# Regulator_Mechanical.net
KiCad netlist of a schematic drawn in Altium Designer
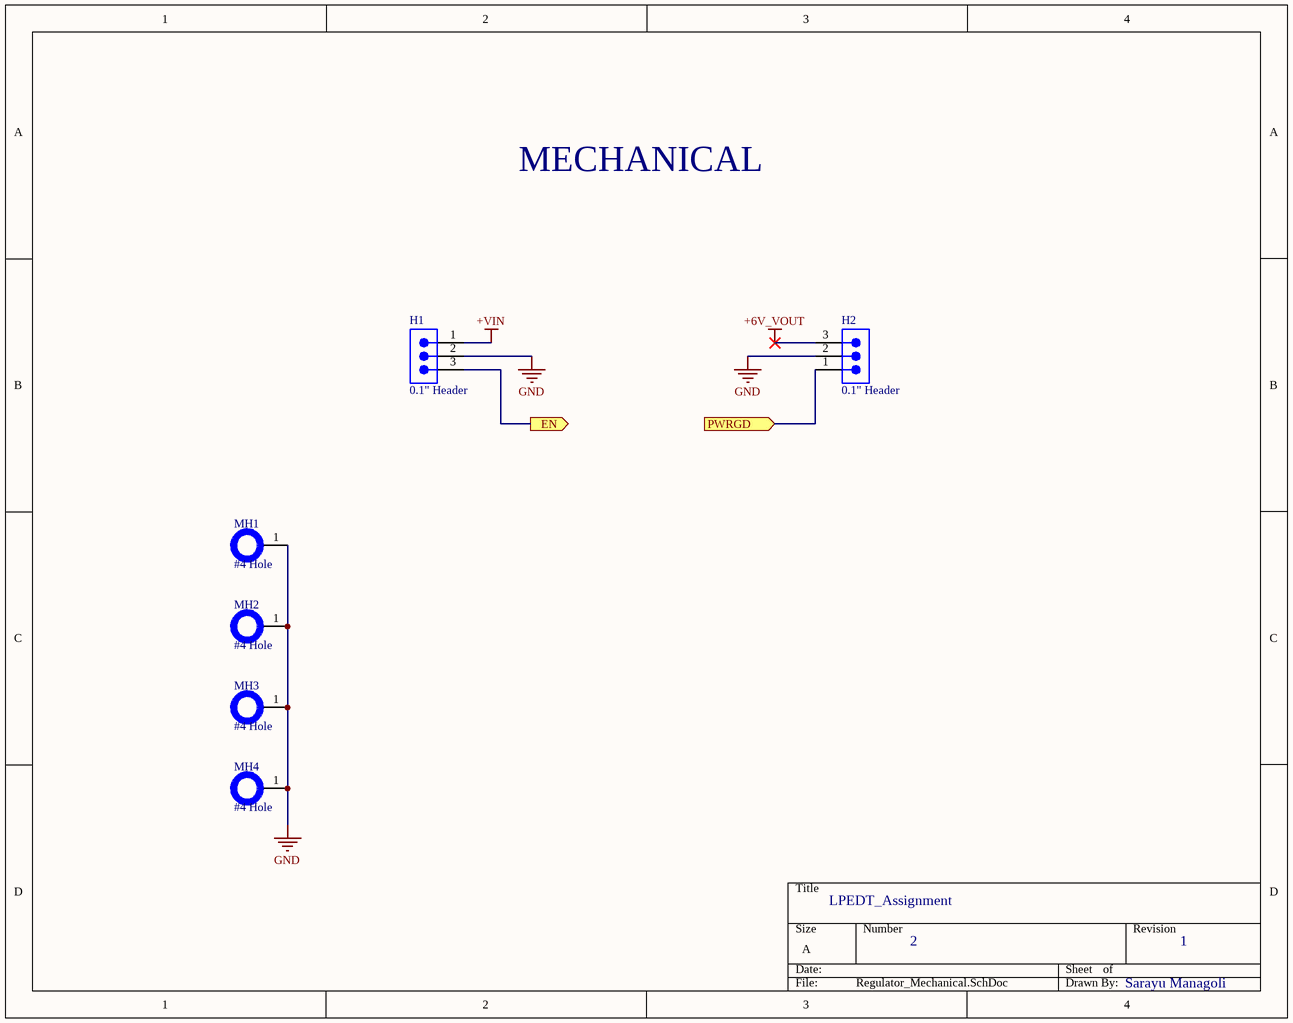
[diagram p0: Regulator_Mechanical.SchDoc]

(export (version "E")
  (design (tool "Eeschema 10.0.6"))
  (components
    (comp (ref "H1")
      (value "0.1\" Header")
      (footprint "3-PIN_MALE_HEADER_01-IN")
      (description "CONN HEADER VERT 3POS 2.54MM")
      (fields
        (field (name "MANUFACTURER") "Sullins")
        (field (name "MANUFACTURER PART NUMBER") "PRPC003SAAN-RC")
      )
      (libsource (lib "LPEDT_Parts") (part "PRPC003SAAN-RC"))
    )
    (comp (ref "H2")
      (value "0.1\" Header")
      (footprint "3-PIN_MALE_HEADER_01-IN")
      (description "CONN HEADER VERT 3POS 2.54MM")
      (fields
        (field (name "MANUFACTURER") "Sullins")
        (field (name "MANUFACTURER PART NUMBER") "PRPC003SAAN-RC")
      )
      (libsource (lib "LPEDT_Parts") (part "PRPC003SAAN-RC"))
    )
    (comp (ref "MH1")
      (value "#4 Hole")
      (footprint "HOLE_#4")
      (libsource (lib "LPEDT_Parts") (part "HOLE_#4"))
    )
    (comp (ref "MH2")
      (value "#4 Hole")
      (footprint "HOLE_#4")
      (libsource (lib "LPEDT_Parts") (part "HOLE_#4"))
    )
    (comp (ref "MH3")
      (value "#4 Hole")
      (footprint "HOLE_#4")
      (libsource (lib "LPEDT_Parts") (part "HOLE_#4"))
    )
    (comp (ref "MH4")
      (value "#4 Hole")
      (footprint "HOLE_#4")
      (libsource (lib "LPEDT_Parts") (part "HOLE_#4"))
    )
  )
  (nets
    (net (code "1") (name "+6V_VOUT") (class "Default")
      (node (ref "H2") (pin "3") (pinfunction "3_3") (pintype "passive"))
    )
    (net (code "2") (name "+VIN") (class "Default")
      (node (ref "H1") (pin "1") (pinfunction "1_1") (pintype "passive"))
    )
    (net (code "3") (name "/EN") (class "Default")
      (node (ref "H1") (pin "3") (pinfunction "3_3") (pintype "passive"))
    )
    (net (code "4") (name "/PWRGD") (class "Default")
      (node (ref "H2") (pin "1") (pinfunction "1_1") (pintype "passive"))
    )
    (net (code "5") (name "GND") (class "Default")
      (node (ref "H1") (pin "2") (pinfunction "2_2") (pintype "passive"))
      (node (ref "H2") (pin "2") (pinfunction "2_2") (pintype "passive"))
      (node (ref "MH1") (pin "1") (pinfunction "1_1") (pintype "passive"))
      (node (ref "MH2") (pin "1") (pinfunction "1_1") (pintype "passive"))
      (node (ref "MH3") (pin "1") (pinfunction "1_1") (pintype "passive"))
      (node (ref "MH4") (pin "1") (pinfunction "1_1") (pintype "passive"))
    )
  )
)
